# mpubreakout.net
KiCad netlist of a schematic drawn in EAGLE
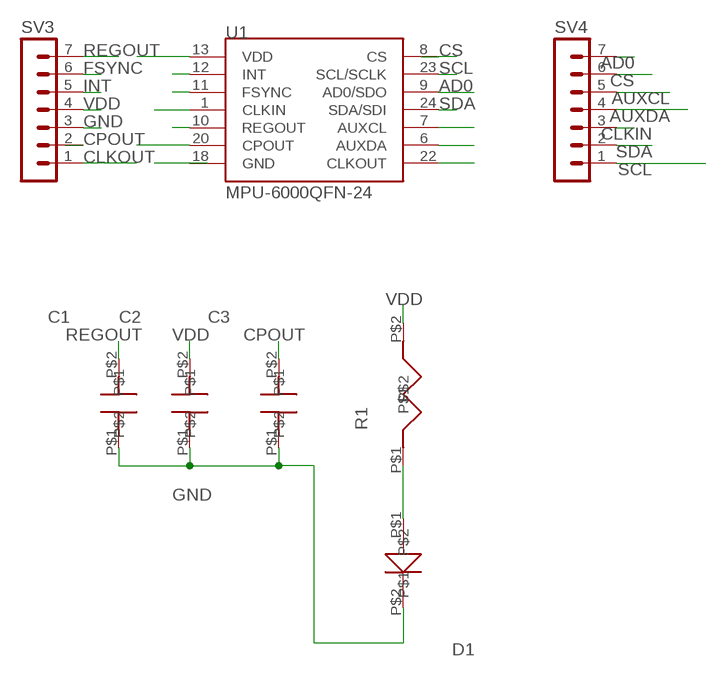
[diagram p0: schematic, sheet 1]

(export (version "E")
  (design (tool "Eeschema 10.0.6"))
  (components
    (comp (ref "C1")
      (value "CAPACITOR-.1UF-4V")
      (footprint "eagle-import:0603-CAPACITOR")
      (libsource (lib "eagle-import") (part "CAPACITOR-.1UF-4V"))
    )
    (comp (ref "C2")
      (value "CAPACITOR-.1UF-4V")
      (footprint "eagle-import:0603-CAPACITOR")
      (libsource (lib "eagle-import") (part "CAPACITOR-.1UF-4V"))
    )
    (comp (ref "C3")
      (value "CAPACITOR-2.2NF-50V")
      (footprint "eagle-import:0603-CAPACITOR")
      (libsource (lib "eagle-import") (part "CAPACITOR-2.2NF-50V"))
    )
    (comp (ref "D1")
      (value "RED_LED")
      (footprint "eagle-import:0603-CAPACITOR")
      (libsource (lib "eagle-import") (part "RED_LED"))
    )
    (comp (ref "R1")
      (value "RESISTOR-4.7K-25V")
      (footprint "eagle-import:0603-CAPACITOR")
      (libsource (lib "eagle-import") (part "RESISTOR-4.7K-25V"))
    )
    (comp (ref "SV3")
      (value "MA07-1")
      (footprint "eagle-import:MA07-1")
      (libsource (lib "eagle-import") (part "MA07-1"))
    )
    (comp (ref "SV4")
      (value "MA07-1")
      (footprint "eagle-import:MA07-1")
      (libsource (lib "eagle-import") (part "MA07-1"))
    )
    (comp (ref "U1")
      (value "MPU-6000QFN-24")
      (footprint "eagle-import:QFN-24-TESTING")
      (libsource (lib "eagle-import") (part "MPU-6000QFN-24"))
    )
  )
  (nets
    (net (code "1") (name "/AD0") (class "Default")
      (node (ref "SV4") (pin "7") (pinfunction "7_7") (pintype "passive"))
      (node (ref "U1") (pin "9") (pinfunction "AD0/SDO_9") (pintype "bidirectional"))
    )
    (net (code "2") (name "/AUXCL") (class "Default")
      (node (ref "SV4") (pin "5") (pinfunction "5_5") (pintype "passive"))
      (node (ref "U1") (pin "7") (pinfunction "AUXCL_7") (pintype "bidirectional"))
    )
    (net (code "3") (name "/AUXDA") (class "Default")
      (node (ref "SV4") (pin "4") (pinfunction "4_4") (pintype "passive"))
      (node (ref "U1") (pin "6") (pinfunction "AUXDA_6") (pintype "bidirectional"))
    )
    (net (code "4") (name "/CLKIN") (class "Default")
      (node (ref "SV4") (pin "3") (pinfunction "3_3") (pintype "passive"))
      (node (ref "U1") (pin "1") (pinfunction "CLKIN_1") (pintype "bidirectional"))
    )
    (net (code "5") (name "/CLKOUT") (class "Default")
      (node (ref "SV3") (pin "1") (pinfunction "1_1") (pintype "passive"))
      (node (ref "U1") (pin "22") (pinfunction "CLKOUT_22") (pintype "bidirectional"))
    )
    (net (code "6") (name "/CPOUT") (class "Default")
      (node (ref "C3") (pin "P$2") (pinfunction "P$2_P$2") (pintype "bidirectional"))
      (node (ref "SV3") (pin "2") (pinfunction "2_2") (pintype "passive"))
      (node (ref "U1") (pin "20") (pinfunction "CPOUT_20") (pintype "bidirectional"))
    )
    (net (code "7") (name "/CS") (class "Default")
      (node (ref "SV4") (pin "6") (pinfunction "6_6") (pintype "passive"))
      (node (ref "U1") (pin "8") (pinfunction "CS_8") (pintype "bidirectional"))
    )
    (net (code "8") (name "/FSYNC") (class "Default")
      (node (ref "SV3") (pin "6") (pinfunction "6_6") (pintype "passive"))
      (node (ref "U1") (pin "11") (pinfunction "FSYNC_11") (pintype "bidirectional"))
    )
    (net (code "9") (name "/GND") (class "Default")
      (node (ref "C1") (pin "P$1") (pinfunction "P$1_P$1") (pintype "bidirectional"))
      (node (ref "C2") (pin "P$1") (pinfunction "P$1_P$1") (pintype "bidirectional"))
      (node (ref "C3") (pin "P$1") (pinfunction "P$1_P$1") (pintype "bidirectional"))
      (node (ref "D1") (pin "P$2") (pinfunction "P$2_P$2") (pintype "bidirectional"))
      (node (ref "SV3") (pin "3") (pinfunction "3_3") (pintype "passive"))
      (node (ref "U1") (pin "18") (pinfunction "GND_18") (pintype "bidirectional"))
    )
    (net (code "10") (name "/INT") (class "Default")
      (node (ref "SV3") (pin "5") (pinfunction "5_5") (pintype "passive"))
      (node (ref "U1") (pin "12") (pinfunction "INT_12") (pintype "bidirectional"))
    )
    (net (code "11") (name "/REGOUT") (class "Default")
      (node (ref "C1") (pin "P$2") (pinfunction "P$2_P$2") (pintype "bidirectional"))
      (node (ref "SV3") (pin "7") (pinfunction "7_7") (pintype "passive"))
      (node (ref "U1") (pin "10") (pinfunction "REGOUT_10") (pintype "bidirectional"))
    )
    (net (code "12") (name "/SCL") (class "Default")
      (node (ref "SV4") (pin "1") (pinfunction "1_1") (pintype "passive"))
      (node (ref "U1") (pin "23") (pinfunction "SCL/SCLK_23") (pintype "bidirectional"))
    )
    (net (code "13") (name "/SDA") (class "Default")
      (node (ref "SV4") (pin "2") (pinfunction "2_2") (pintype "passive"))
      (node (ref "U1") (pin "24") (pinfunction "SDA/SDI_24") (pintype "bidirectional"))
    )
    (net (code "14") (name "/VDD") (class "Default")
      (node (ref "C2") (pin "P$2") (pinfunction "P$2_P$2") (pintype "bidirectional"))
      (node (ref "R1") (pin "P$2") (pinfunction "P$2_P$2") (pintype "bidirectional"))
      (node (ref "SV3") (pin "4") (pinfunction "4_4") (pintype "passive"))
      (node (ref "U1") (pin "13") (pinfunction "VDD_13") (pintype "bidirectional"))
    )
    (net (code "15") (name "Net-(D1-PadP$1)") (class "Default")
      (node (ref "D1") (pin "P$1") (pinfunction "P$1_P$1") (pintype "bidirectional"))
      (node (ref "R1") (pin "P$1") (pinfunction "P$1_P$1") (pintype "bidirectional"))
    )
  )
)
